# Sheet1new.net
KiCad netlist of a schematic drawn in Altium Designer
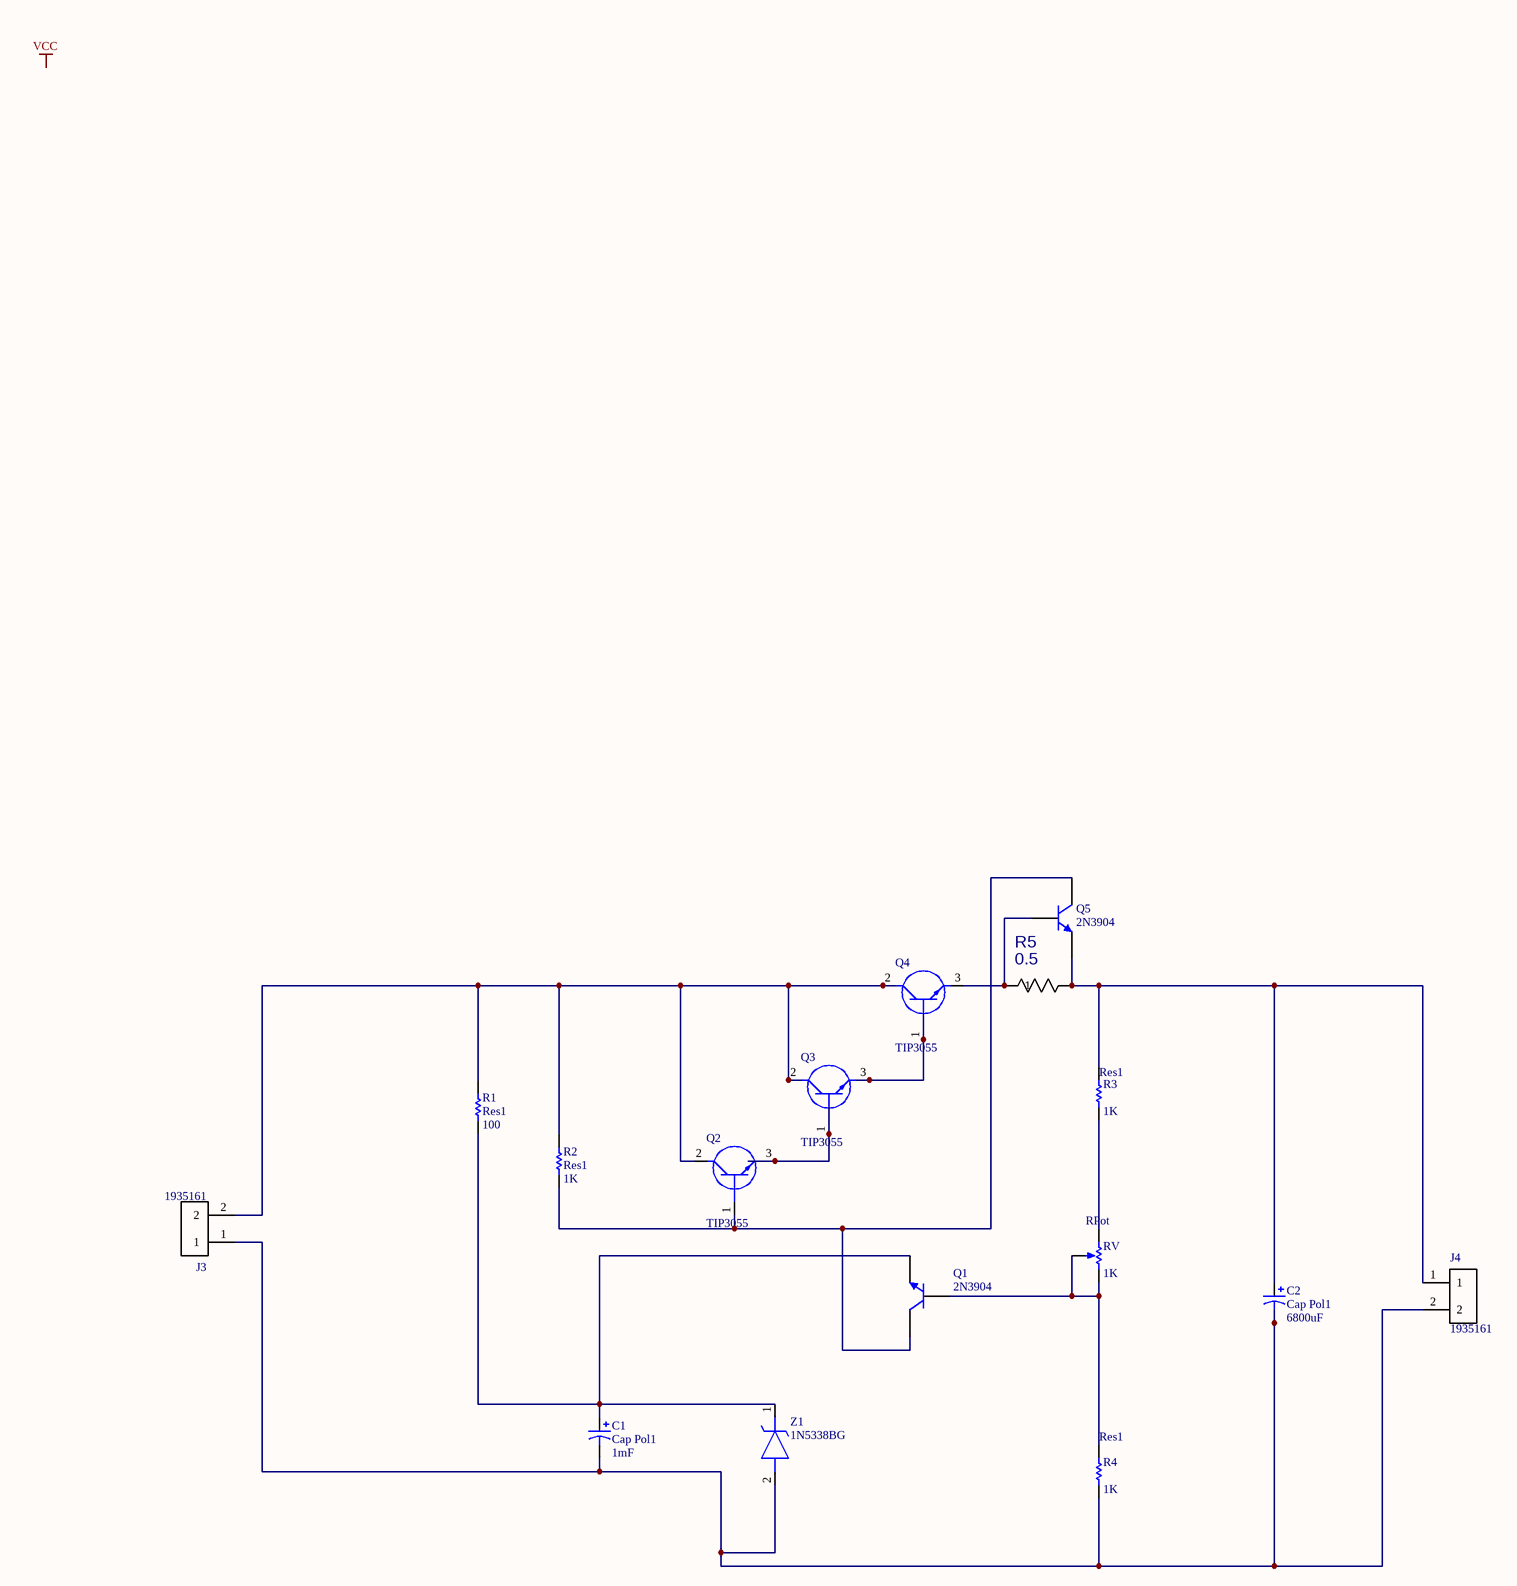
[diagram p0: Sheet1new.SchDoc]

(export (version "E")
  (design (tool "Eeschema 10.0.6"))
  (components
    (comp (ref "C1")
      (value "Cap Pol1")
      (footprint "RB7.6-15")
      (description "Polarized Capacitor (Radial)")
      (fields (field (name "ALTIUM_VALUE") "1mF") (field (name "PUBLISHER") "Altium Limited"))
      (libsource (lib "Miscellaneous Devices") (part "Cap Pol1"))
    )
    (comp (ref "C2")
      (value "Cap Pol1")
      (footprint "RB7.6-15")
      (description "Polarized Capacitor (Radial)")
      (fields (field (name "ALTIUM_VALUE") "6800uF") (field (name "PUBLISHER") "Altium Limited"))
      (libsource (lib "Miscellaneous Devices") (part "Cap Pol1"))
    )
    (comp (ref "J3")
      (value "1935161")
      (footprint "*PHOENIX_1935161")
      (description "Conn Terminal Blocks 2 POS 5mm Solder ST Thru-Hole 16A")
      (fields (field (name "MF") "Phoenix Contact"))
      (libsource (lib "1935161") (part "1935161"))
    )
    (comp (ref "J4")
      (value "1935161")
      (footprint "*PHOENIX_1935161")
      (description "Conn Terminal Blocks 2 POS 5mm Solder ST Thru-Hole 16A")
      (fields (field (name "MF") "Phoenix Contact"))
      (libsource (lib "1935161") (part "1935161"))
    )
    (comp (ref "Q1")
      (value "2N3904")
      (footprint "TO-92A")
      (description "NPN General Purpose Amplifier")
      (fields (field (name "PUBLISHER") "Altium Limited"))
      (libsource (lib "Miscellaneous Devices") (part "2N3904"))
    )
    (comp (ref "Q2")
      (value "TIP3055")
      (footprint "SamacSys:TO545P515X1560X2445-3P")
      (description "Transistor BJT NPN")
      (fields (field (name "MOUSER PART NUMBER") "511-TIP3055") (field (name "RS PART NUMBER") "1686168"))
      (libsource (lib "*") (part "TIP3055"))
    )
    (comp (ref "Q3")
      (value "TIP3055")
      (footprint "SamacSys:TO545P515X1560X2445-3P")
      (description "Transistor BJT NPN")
      (fields (field (name "MOUSER PART NUMBER") "511-TIP3055") (field (name "RS PART NUMBER") "1686168"))
      (libsource (lib "*") (part "TIP3055"))
    )
    (comp (ref "Q4")
      (value "TIP3055")
      (footprint "SamacSys:TO545P515X1560X2445-3P")
      (description "Transistor BJT NPN")
      (fields (field (name "MOUSER PART NUMBER") "511-TIP3055") (field (name "RS PART NUMBER") "1686168"))
      (libsource (lib "*") (part "TIP3055"))
    )
    (comp (ref "Q5")
      (value "2N3904")
      (footprint "TO-92A")
      (description "NPN General Purpose Amplifier")
      (fields (field (name "PUBLISHER") "Altium Limited"))
      (libsource (lib "Miscellaneous Devices") (part "2N3904"))
    )
    (comp (ref "R1")
      (value "Res1")
      (footprint "AXIAL-0.3")
      (description "Resistor")
      (fields (field (name "ALTIUM_VALUE") "100") (field (name "PUBLISHER") "Altium Limited"))
      (libsource (lib "Miscellaneous Devices") (part "Res1"))
    )
    (comp (ref "R2")
      (value "Res1")
      (footprint "AXIAL-0.3")
      (description "Resistor")
      (fields (field (name "ALTIUM_VALUE") "1K") (field (name "PUBLISHER") "Altium Limited"))
      (libsource (lib "Miscellaneous Devices") (part "Res1"))
    )
    (comp (ref "R3")
      (value "Res1")
      (footprint "AXIAL-0.3")
      (description "Resistor")
      (fields (field (name "ALTIUM_VALUE") "1K") (field (name "PUBLISHER") "Altium Limited"))
      (libsource (lib "Miscellaneous Devices") (part "Res1"))
    )
    (comp (ref "R4")
      (value "Res1")
      (footprint "AXIAL-0.3")
      (description "Resistor")
      (fields (field (name "ALTIUM_VALUE") "1K") (field (name "PUBLISHER") "Altium Limited"))
      (libsource (lib "Miscellaneous Devices") (part "Res1"))
    )
    (comp (ref "R5")
      (value "0.5")
      (footprint "RES_TK")
      (fields (field (name "MANUFACTURER_PART_NUMBER") "TK20PR050JE"))
      (libsource (lib "AltiumV15") (part "TK20PR050JE"))
    )
    (comp (ref "RV")
      (value "RPot")
      (footprint "VR5")
      (description "Potentiometer")
      (fields (field (name "ALTIUM_VALUE") "1K") (field (name "PUBLISHER") "Altium Limited"))
      (libsource (lib "Miscellaneous Devices") (part "RPot"))
    )
    (comp (ref "Z1")
      (value "1N5338BG")
      (footprint "SamacSys:DIOAD2260W109L864D349")
      (description "Zener Diode")
      (fields (field (name "MOUSER PART NUMBER") "863-1N5338BG") (field (name "RS PART NUMBER") "0463274P"))
      (libsource (lib "*") (part "1N5338BG"))
    )
  )
  (nets
    (net (code "1") (name "Net-(Q1-B)") (class "Default")
      (node (ref "Q1") (pin "2") (pinfunction "B_2") (pintype "passive"))
      (node (ref "R4") (pin "2") (pinfunction "2_2") (pintype "passive"))
      (node (ref "RV") (pin "2") (pinfunction "BOT_2") (pintype "passive"))
      (node (ref "RV") (pin "3") (pinfunction "TAP_3") (pintype "passive"))
    )
    (net (code "2") (name "Net-(Q1-C)") (class "Default")
      (node (ref "Q1") (pin "3") (pinfunction "C_3") (pintype "passive"))
      (node (ref "Q2") (pin "1") (pinfunction "B_1") (pintype "passive"))
      (node (ref "Q5") (pin "3") (pinfunction "C_3") (pintype "passive"))
      (node (ref "R2") (pin "1") (pinfunction "1_1") (pintype "passive"))
    )
    (net (code "3") (name "Net-(Q1-E)") (class "Default")
      (node (ref "C1") (pin "1") (pinfunction "1_1") (pintype "passive"))
      (node (ref "Q1") (pin "1") (pinfunction "E_1") (pintype "passive"))
      (node (ref "R1") (pin "1") (pinfunction "1_1") (pintype "passive"))
      (node (ref "Z1") (pin "1") (pinfunction "A_1") (pintype "passive"))
    )
    (net (code "4") (name "Net-(Q2-C)") (class "Default")
      (node (ref "J3") (pin "2") (pinfunction "2_2") (pintype "passive"))
      (node (ref "Q2") (pin "2") (pinfunction "C_2") (pintype "passive"))
      (node (ref "Q3") (pin "2") (pinfunction "C_2") (pintype "passive"))
      (node (ref "Q4") (pin "2") (pinfunction "C_2") (pintype "passive"))
      (node (ref "R1") (pin "2") (pinfunction "2_2") (pintype "passive"))
      (node (ref "R2") (pin "2") (pinfunction "2_2") (pintype "passive"))
    )
    (net (code "5") (name "Net-(Q2-E)") (class "Default")
      (node (ref "Q2") (pin "3") (pinfunction "E_3") (pintype "passive"))
      (node (ref "Q3") (pin "1") (pinfunction "B_1") (pintype "passive"))
    )
    (net (code "6") (name "Net-(Q3-E)") (class "Default")
      (node (ref "Q3") (pin "3") (pinfunction "E_3") (pintype "passive"))
      (node (ref "Q4") (pin "1") (pinfunction "B_1") (pintype "passive"))
    )
    (net (code "7") (name "Net-(Q4-E)") (class "Default")
      (node (ref "Q4") (pin "3") (pinfunction "E_3") (pintype "passive"))
      (node (ref "Q5") (pin "2") (pinfunction "B_2") (pintype "passive"))
      (node (ref "R5") (pin "1") (pinfunction "1_1") (pintype "passive"))
    )
    (net (code "8") (name "Net-(Q5-E)") (class "Default")
      (node (ref "C2") (pin "1") (pinfunction "1_1") (pintype "passive"))
      (node (ref "J4") (pin "1") (pinfunction "1_1") (pintype "passive"))
      (node (ref "Q5") (pin "1") (pinfunction "E_1") (pintype "passive"))
      (node (ref "R3") (pin "2") (pinfunction "2_2") (pintype "passive"))
      (node (ref "R5") (pin "2") (pinfunction "2_2") (pintype "passive"))
    )
    (net (code "9") (name "Net-(RV-TOP)") (class "Default")
      (node (ref "R3") (pin "1") (pinfunction "1_1") (pintype "passive"))
      (node (ref "RV") (pin "1") (pinfunction "TOP_1") (pintype "passive"))
    )
    (net (code "10") (name "Net-(Z1-K)") (class "Default")
      (node (ref "C1") (pin "2") (pinfunction "2_2") (pintype "passive"))
      (node (ref "C2") (pin "2") (pinfunction "2_2") (pintype "passive"))
      (node (ref "J3") (pin "1") (pinfunction "1_1") (pintype "passive"))
      (node (ref "J4") (pin "2") (pinfunction "2_2") (pintype "passive"))
      (node (ref "R4") (pin "1") (pinfunction "1_1") (pintype "passive"))
      (node (ref "Z1") (pin "2") (pinfunction "K_2") (pintype "passive"))
    )
  )
)
